# 780-00019_Rev2_Pg1.net
KiCad netlist of a schematic drawn in Altium Designer
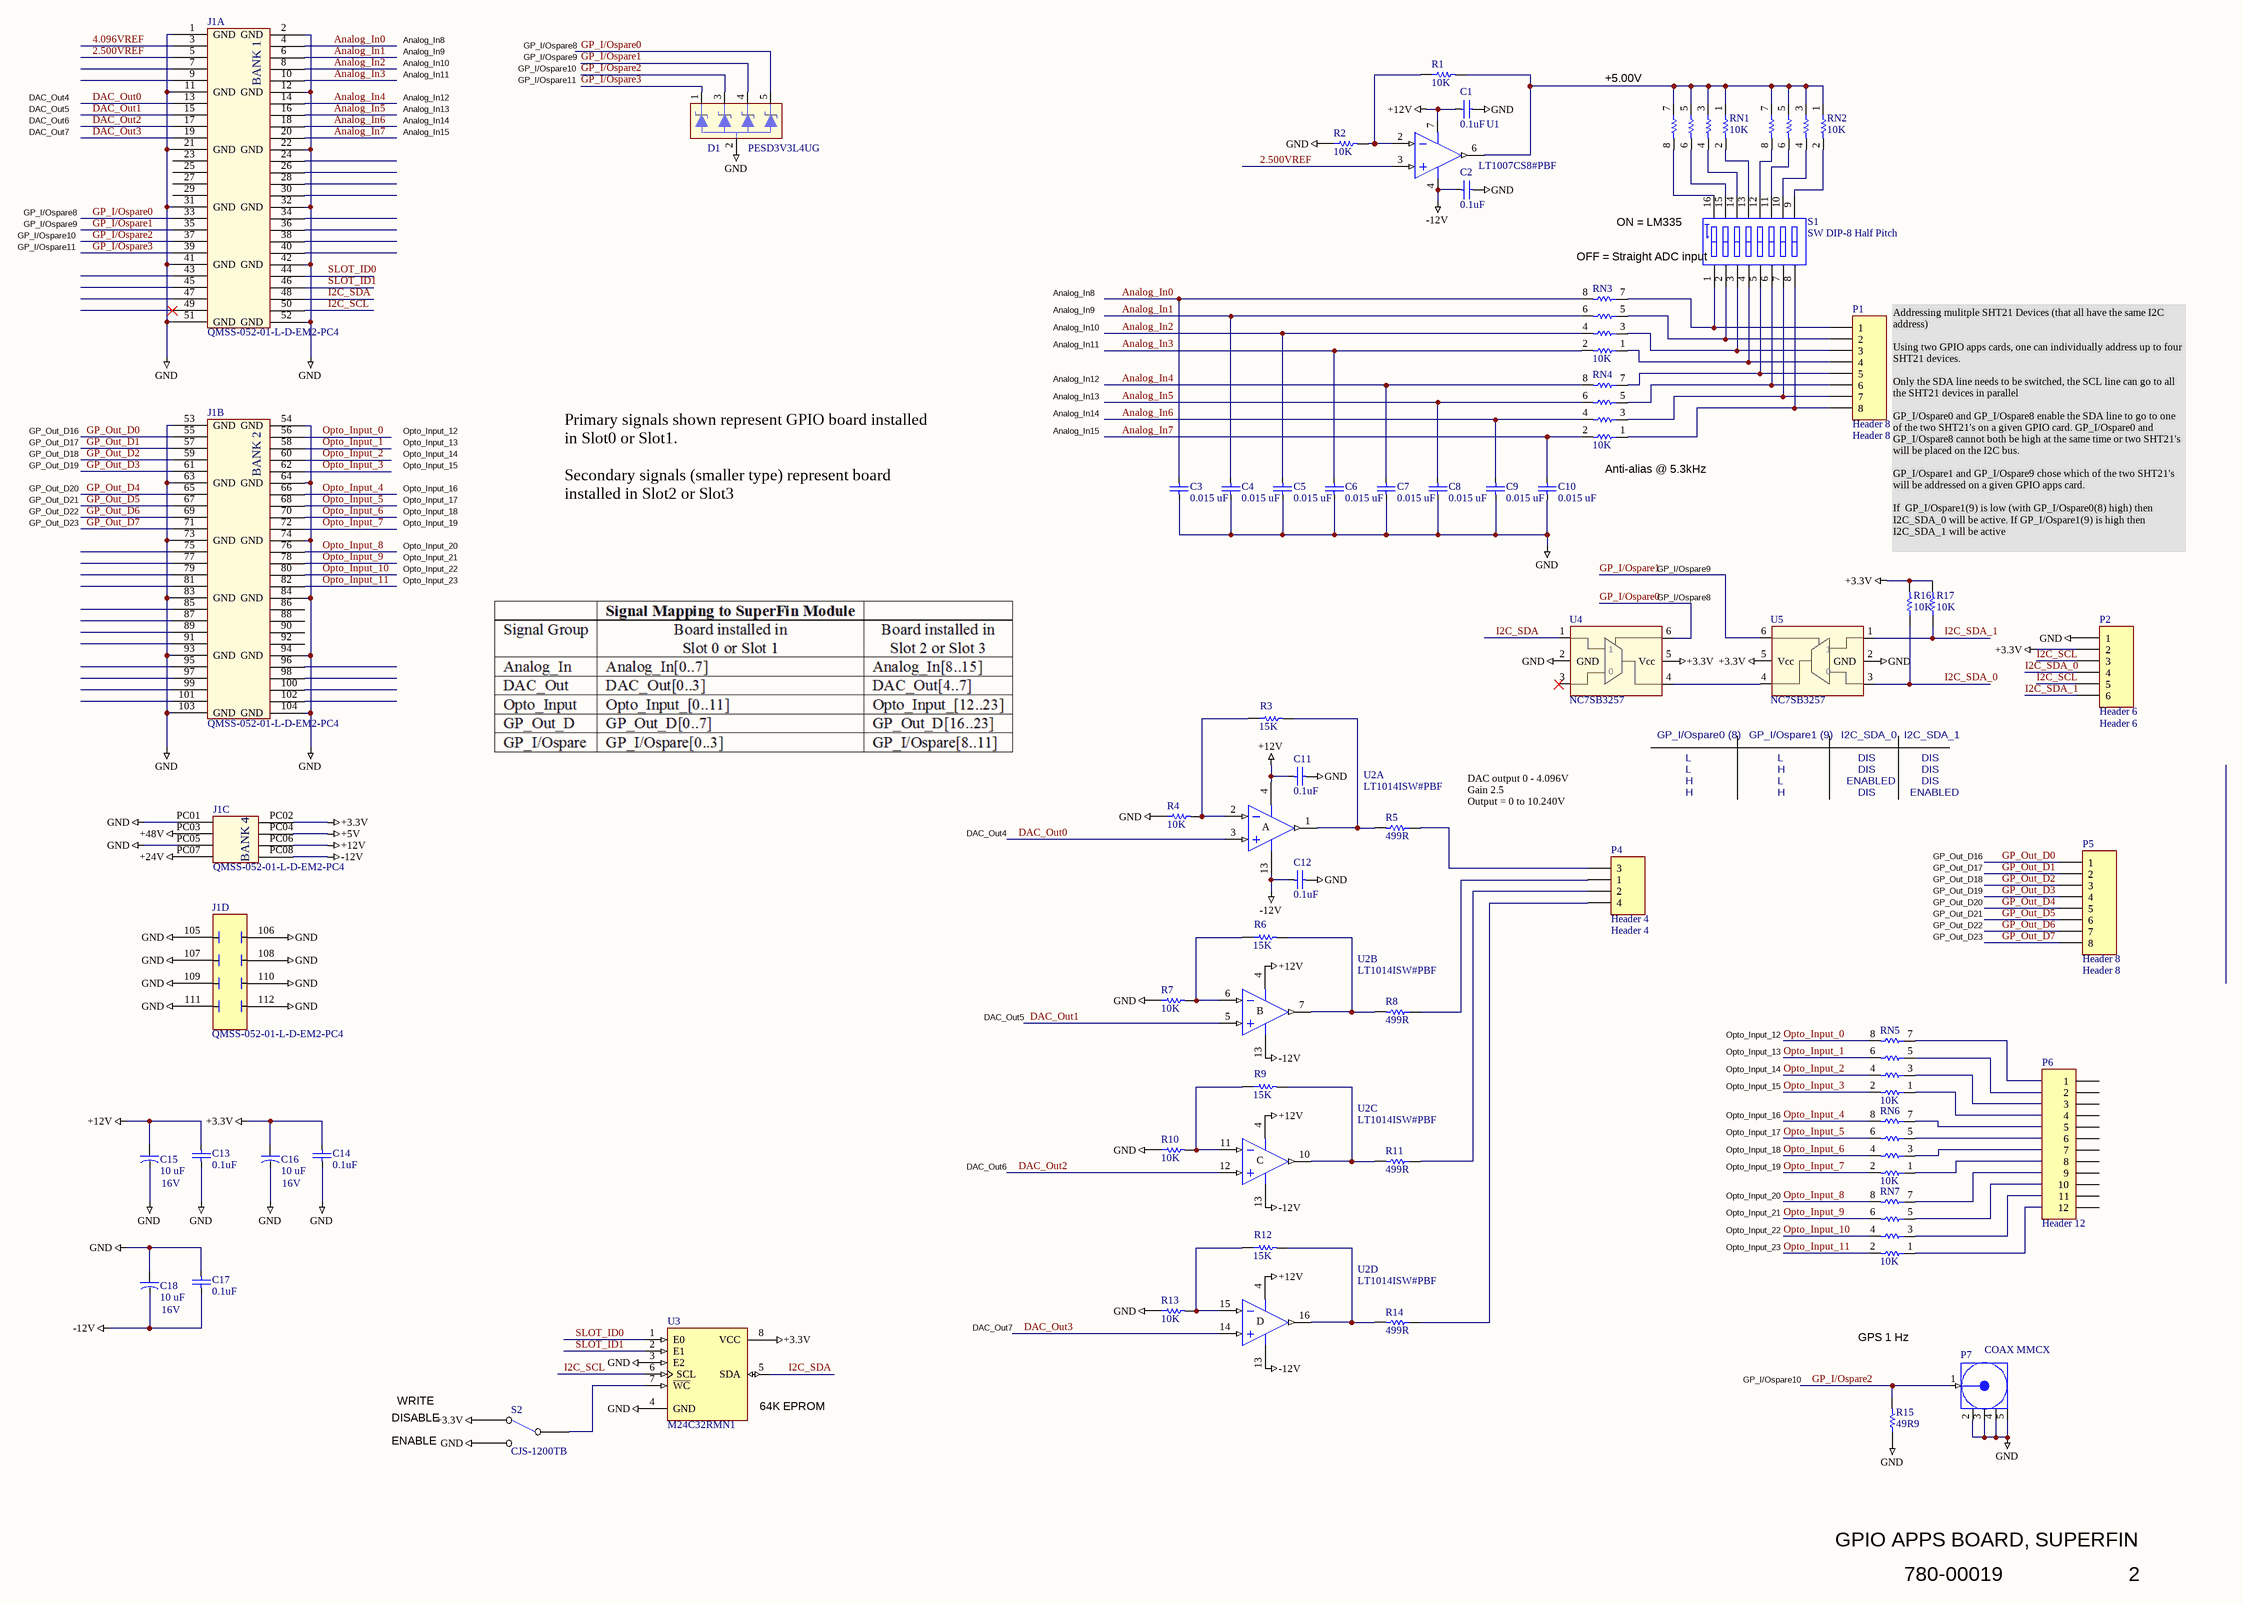
[diagram p0: 780-00019 Rev2 Pg1.SchDoc]

(export (version "E")
  (design (tool "Eeschema 10.0.6"))
  (components
    (comp (ref "C1")
      (value "0.1uF")
      (footprint "SMD_0805")
      (description "Capacitor")
      (fields (field (name "Comment") "Cap SMD"))
      (libsource (lib "Richs Schematic Components") (part "Cap SMD"))
    )
    (comp (ref "C2")
      (value "0.1uF")
      (footprint "SMD_0805")
      (description "Capacitor")
      (fields (field (name "Comment") "Cap SMD"))
      (libsource (lib "Richs Schematic Components") (part "Cap SMD"))
    )
    (comp (ref "C3")
      (value "0.015 uF")
      (footprint "SMD_0805")
      (description "Capacitor NP0")
      (fields (field (name "MANUFACTURER") "Murata") (field (name "Comment") "Cap SMD"))
      (libsource (lib "Richs Schematic Components") (part "Cap SMD"))
    )
    (comp (ref "C4")
      (value "0.015 uF")
      (footprint "SMD_0805")
      (description "Capacitor NP0")
      (fields (field (name "MANUFACTURER") "Murata") (field (name "Comment") "Cap SMD"))
      (libsource (lib "Richs Schematic Components") (part "Cap SMD"))
    )
    (comp (ref "C5")
      (value "0.015 uF")
      (footprint "SMD_0805")
      (description "Capacitor NP0")
      (fields (field (name "MANUFACTURER") "Murata") (field (name "Comment") "Cap SMD"))
      (libsource (lib "Richs Schematic Components") (part "Cap SMD"))
    )
    (comp (ref "C6")
      (value "0.015 uF")
      (footprint "SMD_0805")
      (description "Capacitor NP0")
      (fields (field (name "MANUFACTURER") "Murata") (field (name "Comment") "Cap SMD"))
      (libsource (lib "Richs Schematic Components") (part "Cap SMD"))
    )
    (comp (ref "C7")
      (value "0.015 uF")
      (footprint "SMD_0805")
      (description "Capacitor NP0")
      (fields (field (name "MANUFACTURER") "Murata") (field (name "Comment") "Cap SMD"))
      (libsource (lib "Richs Schematic Components") (part "Cap SMD"))
    )
    (comp (ref "C8")
      (value "0.015 uF")
      (footprint "SMD_0805")
      (description "Capacitor NP0")
      (fields (field (name "MANUFACTURER") "Murata") (field (name "Comment") "Cap SMD"))
      (libsource (lib "Richs Schematic Components") (part "Cap SMD"))
    )
    (comp (ref "C9")
      (value "0.015 uF")
      (footprint "SMD_0805")
      (description "Capacitor NP0")
      (fields (field (name "MANUFACTURER") "Murata") (field (name "Comment") "Cap SMD"))
      (libsource (lib "Richs Schematic Components") (part "Cap SMD"))
    )
    (comp (ref "C10")
      (value "0.015 uF")
      (footprint "SMD_0805")
      (description "Capacitor NP0")
      (fields (field (name "MANUFACTURER") "Murata") (field (name "Comment") "Cap SMD"))
      (libsource (lib "Richs Schematic Components") (part "Cap SMD"))
    )
    (comp (ref "C11")
      (value "0.1uF")
      (footprint "SMD_0805")
      (description "Capacitor")
      (fields (field (name "Comment") "Cap SMD"))
      (libsource (lib "Richs Schematic Components") (part "Cap SMD"))
    )
    (comp (ref "C12")
      (value "0.1uF")
      (footprint "SMD_0805")
      (description "Capacitor")
      (fields (field (name "Comment") "Cap SMD"))
      (libsource (lib "Richs Schematic Components") (part "Cap SMD"))
    )
    (comp (ref "C13")
      (value "0.1uF")
      (footprint "SMD_0805")
      (description "Capacitor")
      (fields (field (name "Comment") "Cap SMD"))
      (libsource (lib "Richs Schematic Components") (part "Cap SMD"))
    )
    (comp (ref "C14")
      (value "0.1uF")
      (footprint "SMD_0805")
      (description "Capacitor")
      (fields (field (name "Comment") "Cap SMD"))
      (libsource (lib "Richs Schematic Components") (part "Cap SMD"))
    )
    (comp (ref "C15")
      (value "16V")
      (footprint "SMD_CAP_3216")
      (description "outline 3.2mm x 1.6mm")
      (fields (field (name "MANUFACTURER") "KEMET") (field (name "ALTIUM_VALUE") "10 uF"))
      (libsource (lib "Richs Schematic Components") (part "Cap Tant 16V"))
    )
    (comp (ref "C16")
      (value "16V")
      (footprint "SMD_CAP_3216")
      (description "outline 3.2mm x 1.6mm")
      (fields (field (name "MANUFACTURER") "KEMET") (field (name "ALTIUM_VALUE") "10 uF"))
      (libsource (lib "Richs Schematic Components") (part "Cap Tant 16V"))
    )
    (comp (ref "C17")
      (value "0.1uF")
      (footprint "SMD_0805")
      (description "Capacitor")
      (fields (field (name "Comment") "Cap SMD"))
      (libsource (lib "Richs Schematic Components") (part "Cap SMD"))
    )
    (comp (ref "C18")
      (value "16V")
      (footprint "SMD_CAP_3216")
      (description "outline 3.2mm x 1.6mm")
      (fields (field (name "MANUFACTURER") "KEMET") (field (name "ALTIUM_VALUE") "10 uF"))
      (libsource (lib "Richs Schematic Components") (part "Cap Tant 16V"))
    )
    (comp (ref "D1")
      (value "PESD3V3L4UG")
      (footprint "SOT-353")
      (description "Quad ESD Diode 3.3V")
      (fields (field (name "MANUFACTURER") "NXP"))
      (libsource (lib "Richs Schematic Components") (part "ESD Diode 3.3V Quad"))
    )
    (comp (ref "J1")
      (value "QMSS-052-01-L-D-EM2-PC4")
      (footprint "QMS EDGE PWR PINS - 104 pin")
      (description "SAMTEC QMSS EDGE W/PWR PINS")
      (fields (field (name "MANUFACTURER") "SAMTEC") (field (name "Comment") "QMSS-EM-PC4-104pin"))
      (libsource (lib "Richs Schematic Components") (part "QMSS-EM-PC4-104pin"))
    )
    (comp (ref "P1")
      (value "Header 8")
      (footprint "HDR1X8 for IDC")
      (description "Header, 8-Pin")
      (fields (field (name "MANUFACTURER") "tyco") (field (name "ALTIUM_VALUE") "Header 8"))
      (libsource (lib "Richs Schematic Components") (part "Header 8"))
    )
    (comp (ref "P2")
      (value "Header 6")
      (footprint "HDR1X6 for IDC")
      (description "Header, 6-Pin")
      (fields (field (name "ALTIUM_VALUE") "Header 6"))
      (libsource (lib "Richs Schematic Components") (part "Header 6"))
    )
    (comp (ref "P4")
      (value "Header 4")
      (footprint "HDR1X4 for IDC")
      (description "Header, 4-Pin")
      (fields (field (name "ALTIUM_VALUE") "Header 4"))
      (libsource (lib "Richs Schematic Components") (part "Header 4"))
    )
    (comp (ref "P5")
      (value "Header 8")
      (footprint "HDR1X8 for IDC")
      (description "Header, 8-Pin")
      (fields (field (name "MANUFACTURER") "tyco") (field (name "ALTIUM_VALUE") "Header 8"))
      (libsource (lib "Richs Schematic Components") (part "Header 8"))
    )
    (comp (ref "P6")
      (value "Header 12")
      (footprint "HDR1X12 for IDC")
      (description "Header, 12-Pin")
      (fields (field (name "MANUFACTURER") "Tyco"))
      (libsource (lib "Richs Schematic Components") (part "Header 12"))
    )
    (comp (ref "P7")
      (value "COAX MMCX")
      (footprint "Miscellaneous Connectors:MMCX2.54-V5")
      (description "RF Coaxial PCB Connector, MMCX; Thru-Hole, Vertical Mount Plug,  50 Ohm Impedance")
      (fields (field (name "MANUFACTURER") "Emerson"))
      (libsource (lib "Richs Schematic Components") (part "COAX-M"))
    )
    (comp (ref "R1")
      (value "10K")
      (footprint "SMD_0805")
      (description "Resistor 0805")
      (fields (field (name "MANUFACTURER") "Vishay/Dale") (field (name "Comment") "Res 0805"))
      (libsource (lib "Richs Schematic Components") (part "Res SMD"))
    )
    (comp (ref "R2")
      (value "10K")
      (footprint "SMD_0805")
      (description "Resistor 0805")
      (fields (field (name "MANUFACTURER") "Vishay/Dale") (field (name "Comment") "Res 0805"))
      (libsource (lib "Richs Schematic Components") (part "Res SMD"))
    )
    (comp (ref "R3")
      (value "15K")
      (footprint "SMD_0805")
      (description "Resistor 0805")
      (fields (field (name "MANUFACTURER") "Vishay/Dale") (field (name "Comment") "Res 0805"))
      (libsource (lib "Richs Schematic Components") (part "Res SMD"))
    )
    (comp (ref "R4")
      (value "10K")
      (footprint "SMD_0805")
      (description "Resistor 0805")
      (fields (field (name "MANUFACTURER") "Vishay/Dale") (field (name "Comment") "Res 0805"))
      (libsource (lib "Richs Schematic Components") (part "Res SMD"))
    )
    (comp (ref "R5")
      (value "499R")
      (footprint "SMD_0805")
      (description "Resistor 0805")
      (fields (field (name "MANUFACTURER") "Vishay/Dale") (field (name "Comment") "Res 0805"))
      (libsource (lib "Richs Schematic Components") (part "Res SMD"))
    )
    (comp (ref "R6")
      (value "15K")
      (footprint "SMD_0805")
      (description "Resistor 0805")
      (fields (field (name "MANUFACTURER") "Vishay/Dale") (field (name "Comment") "Res 0805"))
      (libsource (lib "Richs Schematic Components") (part "Res SMD"))
    )
    (comp (ref "R7")
      (value "10K")
      (footprint "SMD_0805")
      (description "Resistor 0805")
      (fields (field (name "MANUFACTURER") "Vishay/Dale") (field (name "Comment") "Res 0805"))
      (libsource (lib "Richs Schematic Components") (part "Res SMD"))
    )
    (comp (ref "R8")
      (value "499R")
      (footprint "SMD_0805")
      (description "Resistor 0805")
      (fields (field (name "MANUFACTURER") "Vishay/Dale") (field (name "Comment") "Res 0805"))
      (libsource (lib "Richs Schematic Components") (part "Res SMD"))
    )
    (comp (ref "R9")
      (value "15K")
      (footprint "SMD_0805")
      (description "Resistor 0805")
      (fields (field (name "MANUFACTURER") "Vishay/Dale") (field (name "Comment") "Res 0805"))
      (libsource (lib "Richs Schematic Components") (part "Res SMD"))
    )
    (comp (ref "R10")
      (value "10K")
      (footprint "SMD_0805")
      (description "Resistor 0805")
      (fields (field (name "MANUFACTURER") "Vishay/Dale") (field (name "Comment") "Res 0805"))
      (libsource (lib "Richs Schematic Components") (part "Res SMD"))
    )
    (comp (ref "R11")
      (value "499R")
      (footprint "SMD_0805")
      (description "Resistor 0805")
      (fields (field (name "MANUFACTURER") "Vishay/Dale") (field (name "Comment") "Res 0805"))
      (libsource (lib "Richs Schematic Components") (part "Res SMD"))
    )
    (comp (ref "R12")
      (value "15K")
      (footprint "SMD_0805")
      (description "Resistor 0805")
      (fields (field (name "MANUFACTURER") "Vishay/Dale") (field (name "Comment") "Res 0805"))
      (libsource (lib "Richs Schematic Components") (part "Res SMD"))
    )
    (comp (ref "R13")
      (value "10K")
      (footprint "SMD_0805")
      (description "Resistor 0805")
      (fields (field (name "MANUFACTURER") "Vishay/Dale") (field (name "Comment") "Res 0805"))
      (libsource (lib "Richs Schematic Components") (part "Res SMD"))
    )
    (comp (ref "R14")
      (value "499R")
      (footprint "SMD_0805")
      (description "Resistor 0805")
      (fields (field (name "MANUFACTURER") "Vishay/Dale") (field (name "Comment") "Res 0805"))
      (libsource (lib "Richs Schematic Components") (part "Res SMD"))
    )
    (comp (ref "R15")
      (value "49R9")
      (footprint "SMD_0805")
      (description "Resistor 0805")
      (fields (field (name "MANUFACTURER") "Vishay/Dale") (field (name "Comment") "Res 0805"))
      (libsource (lib "Richs Schematic Components") (part "Res SMD"))
    )
    (comp (ref "R16")
      (value "10K")
      (footprint "SMD_0805")
      (description "Resistor 0805")
      (fields (field (name "MANUFACTURER") "Vishay/Dale") (field (name "Comment") "Res 0805"))
      (libsource (lib "Richs Schematic Components") (part "Res SMD"))
    )
    (comp (ref "R17")
      (value "10K")
      (footprint "SMD_0805")
      (description "Resistor 0805")
      (fields (field (name "MANUFACTURER") "Vishay/Dale") (field (name "Comment") "Res 0805"))
      (libsource (lib "Richs Schematic Components") (part "Res SMD"))
    )
    (comp (ref "RN1")
      (value "10K")
      (footprint "RES ARRAY 0603 x 4")
      (description "Resistor Array 4 Isolated")
      (fields (field (name "MANUFACTURER") "PANASONIC - ECG") (field (name "Comment") "RES ARRAY  x4 10K"))
      (libsource (lib "Richs Schematic Components") (part "RES ARRAY  x4 10K"))
    )
    (comp (ref "RN2")
      (value "10K")
      (footprint "RES ARRAY 0603 x 4")
      (description "Resistor Array 4 Isolated")
      (fields (field (name "MANUFACTURER") "PANASONIC - ECG") (field (name "Comment") "RES ARRAY  x4 10K"))
      (libsource (lib "Richs Schematic Components") (part "RES ARRAY  x4 10K"))
    )
    (comp (ref "RN3")
      (value "10K")
      (footprint "RES ARRAY 0603 x 4")
      (description "Resistor Array 4 Isolated")
      (fields (field (name "MANUFACTURER") "PANASONIC - ECG") (field (name "Comment") "RES ARRAY  x4 10K"))
      (libsource (lib "Richs Schematic Components") (part "RES ARRAY  x4 10K"))
    )
    (comp (ref "RN4")
      (value "10K")
      (footprint "RES ARRAY 0603 x 4")
      (description "Resistor Array 4 Isolated")
      (fields (field (name "MANUFACTURER") "PANASONIC - ECG") (field (name "Comment") "RES ARRAY  x4 10K"))
      (libsource (lib "Richs Schematic Components") (part "RES ARRAY  x4 10K"))
    )
    (comp (ref "RN5")
      (value "10K")
      (footprint "RES ARRAY 0603 x 4")
      (description "Resistor Array 4 Isolated")
      (fields (field (name "MANUFACTURER") "PANASONIC - ECG") (field (name "Comment") "RES ARRAY  x4 10K"))
      (libsource (lib "Richs Schematic Components") (part "RES ARRAY  x4 10K"))
    )
    (comp (ref "RN6")
      (value "10K")
      (footprint "RES ARRAY 0603 x 4")
      (description "Resistor Array 4 Isolated")
      (fields (field (name "MANUFACTURER") "PANASONIC - ECG") (field (name "Comment") "RES ARRAY  x4 10K"))
      (libsource (lib "Richs Schematic Components") (part "RES ARRAY  x4 10K"))
    )
    (comp (ref "RN7")
      (value "10K")
      (footprint "RES ARRAY 0603 x 4")
      (description "Resistor Array 4 Isolated")
      (fields (field (name "MANUFACTURER") "PANASONIC - ECG") (field (name "Comment") "RES ARRAY  x4 10K"))
      (libsource (lib "Richs Schematic Components") (part "RES ARRAY  x4 10K"))
    )
    (comp (ref "S1")
      (value "SW DIP-8 Half Pitch")
      (footprint "SW DIP 8 pos half pitch")
      (description "DIP Switch, 8 Position, SPST")
      (fields (field (name "MANUFACTURER") "GrayHill"))
      (libsource (lib "Richs Schematic Components") (part "SW DIP-8 Half Pitch"))
    )
    (comp (ref "S2")
      (value "CJS-1200TB")
      (footprint "CAS-120B")
      (fields (field (name "MANUFACTURER") "Copal Electronics"))
      (libsource (lib "JON_1_Library") (part "SW_SPDT_DOUG"))
    )
    (comp (ref "U1")
      (value "LT1007CS8#PBF")
      (footprint "S8_M")
      (description "Low Noise BJT input opamp")
      (fields (field (name "MANUFACTURER") "Linear Tech"))
      (libsource (lib "Richs Schematic Components") (part "LT1007CS8#PBF"))
    )
    (comp (ref "U2")
      (value "LT1014ISW#PBF")
      (footprint "SW16_N")
      (description "Quad Precision Operational Amplifier")
      (fields (field (name "MANUFACTURER") "Linear Tech"))
      (libsource (lib "LT Operational Amplifier") (part "LT1014ISW#PBF"))
    )
    (comp (ref "U3")
      (value "M24C32RMN1")
      (footprint "SOP8_N")
      (description "32 Kbit Serial I²C Bus EEPROM")
      (fields (field (name "MANUFACTURER") "ST Micro"))
      (libsource (lib "ST Memory EEPROM Serial") (part "M24C32RMN1"))
    )
    (comp (ref "U4")
      (value "NC7SB3257")
      (footprint "SC70-LT6_M")
      (description "Mux/Demux Bus Switch")
      (fields (field (name "MANUFACTURER") "Fairchild"))
      (libsource (lib "") (part "MUX 2{colon}1_1"))
    )
    (comp (ref "U5")
      (value "NC7SB3257")
      (footprint "SC70-LT6_M")
      (description "Mux/Demux Bus Switch")
      (fields (field (name "MANUFACTURER") "Fairchild"))
      (libsource (lib "Richs Schematic Components") (part "MUX 2{colon}1"))
    )
  )
  (nets
    (net (code "1") (name "+3.3V") (class "Default")
      (node (ref "C14") (pin "1") (pinfunction "1_1") (pintype "passive"))
      (node (ref "C16") (pin "1") (pinfunction "1_1") (pintype "passive"))
      (node (ref "J1") (pin "PC02") (pinfunction "PC02_PC02") (pintype "passive"))
      (node (ref "P2") (pin "2") (pinfunction "2_2") (pintype "passive"))
      (node (ref "R16") (pin "2") (pinfunction "2_2") (pintype "passive"))
      (node (ref "R17") (pin "2") (pinfunction "2_2") (pintype "passive"))
      (node (ref "S2") (pin "3") (pinfunction "NC_3") (pintype "passive"))
      (node (ref "U3") (pin "8") (pinfunction "VCC_8") (pintype "power_in"))
      (node (ref "U4") (pin "5") (pinfunction "Vcc_5") (pintype "passive"))
      (node (ref "U5") (pin "5") (pinfunction "Vcc_5") (pintype "passive"))
    )
    (net (code "2") (name "+5V") (class "Default")
      (node (ref "J1") (pin "PC04") (pinfunction "PC04_PC04") (pintype "passive"))
    )
    (net (code "3") (name "+12V") (class "Default")
      (node (ref "C1") (pin "1") (pinfunction "1_1") (pintype "passive"))
      (node (ref "C11") (pin "1") (pinfunction "1_1") (pintype "passive"))
      (node (ref "C13") (pin "1") (pinfunction "1_1") (pintype "passive"))
      (node (ref "C15") (pin "1") (pinfunction "1_1") (pintype "passive"))
      (node (ref "J1") (pin "PC06") (pinfunction "PC06_PC06") (pintype "passive"))
      (node (ref "U1") (pin "7") (pinfunction "V+_7") (pintype "power_in"))
      (node (ref "U2") (pin "4") (pinfunction "V+_4") (pintype "power_in"))
    )
    (net (code "4") (name "+24V") (class "Default")
      (node (ref "J1") (pin "PC07") (pinfunction "PC07_PC07") (pintype "passive"))
    )
    (net (code "5") (name "+48V") (class "Default")
      (node (ref "J1") (pin "PC03") (pinfunction "PC03_PC03") (pintype "passive"))
    )
    (net (code "6") (name "-12V") (class "Default")
      (node (ref "C12") (pin "1") (pinfunction "1_1") (pintype "passive"))
      (node (ref "C17") (pin "2") (pinfunction "2_2") (pintype "passive"))
      (node (ref "C18") (pin "2") (pinfunction "2_2") (pintype "passive"))
      (node (ref "C2") (pin "1") (pinfunction "1_1") (pintype "passive"))
      (node (ref "J1") (pin "PC08") (pinfunction "PC08_PC08") (pintype "passive"))
      (node (ref "U1") (pin "4") (pinfunction "V-_4") (pintype "power_in"))
      (node (ref "U2") (pin "13") (pinfunction "V-_13") (pintype "power_in"))
    )
    (net (code "7") (name "/2.500VREF") (class "Default")
      (node (ref "J1") (pin "5") (pinfunction "5_5") (pintype "passive"))
      (node (ref "U1") (pin "3") (pinfunction "IN+_3") (pintype "input"))
    )
    (net (code "8") (name "/4.096VREF") (class "Default")
      (node (ref "J1") (pin "3") (pinfunction "3_3") (pintype "passive"))
    )
    (net (code "9") (name "/Analog_In0") (class "Default")
      (node (ref "C3") (pin "2") (pinfunction "2_2") (pintype "passive"))
      (node (ref "J1") (pin "4") (pinfunction "4_4") (pintype "passive"))
      (node (ref "RN3") (pin "8") (pinfunction "8_8") (pintype "passive"))
    )
    (net (code "10") (name "/Analog_In1") (class "Default")
      (node (ref "C4") (pin "2") (pinfunction "2_2") (pintype "passive"))
      (node (ref "J1") (pin "6") (pinfunction "6_6") (pintype "passive"))
      (node (ref "RN3") (pin "6") (pinfunction "6_6") (pintype "passive"))
    )
    (net (code "11") (name "/Analog_In2") (class "Default")
      (node (ref "C5") (pin "2") (pinfunction "2_2") (pintype "passive"))
      (node (ref "J1") (pin "8") (pinfunction "8_8") (pintype "passive"))
      (node (ref "RN3") (pin "4") (pinfunction "4_4") (pintype "passive"))
    )
    (net (code "12") (name "/Analog_In3") (class "Default")
      (node (ref "C6") (pin "2") (pinfunction "2_2") (pintype "passive"))
      (node (ref "J1") (pin "10") (pinfunction "10_10") (pintype "passive"))
      (node (ref "RN3") (pin "2") (pinfunction "2_2") (pintype "passive"))
    )
    (net (code "13") (name "/Analog_In4") (class "Default")
      (node (ref "C7") (pin "2") (pinfunction "2_2") (pintype "passive"))
      (node (ref "J1") (pin "14") (pinfunction "14_14") (pintype "passive"))
      (node (ref "RN4") (pin "8") (pinfunction "8_8") (pintype "passive"))
    )
    (net (code "14") (name "/Analog_In5") (class "Default")
      (node (ref "C8") (pin "2") (pinfunction "2_2") (pintype "passive"))
      (node (ref "J1") (pin "16") (pinfunction "16_16") (pintype "passive"))
      (node (ref "RN4") (pin "6") (pinfunction "6_6") (pintype "passive"))
    )
    (net (code "15") (name "/Analog_In6") (class "Default")
      (node (ref "C9") (pin "2") (pinfunction "2_2") (pintype "passive"))
      (node (ref "J1") (pin "18") (pinfunction "18_18") (pintype "passive"))
      (node (ref "RN4") (pin "4") (pinfunction "4_4") (pintype "passive"))
    )
    (net (code "16") (name "/Analog_In7") (class "Default")
      (node (ref "C10") (pin "2") (pinfunction "2_2") (pintype "passive"))
      (node (ref "J1") (pin "20") (pinfunction "20_20") (pintype "passive"))
      (node (ref "RN4") (pin "2") (pinfunction "2_2") (pintype "passive"))
    )
    (net (code "17") (name "/DAC_Out0") (class "Default")
      (node (ref "J1") (pin "13") (pinfunction "13_13") (pintype "passive"))
      (node (ref "U2") (pin "3") (pinfunction "IN+_3") (pintype "input"))
    )
    (net (code "18") (name "/DAC_Out1") (class "Default")
      (node (ref "J1") (pin "15") (pinfunction "15_15") (pintype "passive"))
      (node (ref "U2") (pin "5") (pinfunction "IN+_5") (pintype "input"))
    )
    (net (code "19") (name "/DAC_Out2") (class "Default")
      (node (ref "J1") (pin "17") (pinfunction "17_17") (pintype "passive"))
      (node (ref "U2") (pin "12") (pinfunction "IN+_12") (pintype "input"))
    )
    (net (code "20") (name "/DAC_Out3") (class "Default")
      (node (ref "J1") (pin "19") (pinfunction "19_19") (pintype "passive"))
      (node (ref "U2") (pin "14") (pinfunction "IN+_14") (pintype "input"))
    )
    (net (code "21") (name "/GP_I{slash}Ospare0") (class "Default")
      (node (ref "D1") (pin "5") (pintype "passive"))
      (node (ref "J1") (pin "33") (pinfunction "33_33") (pintype "passive"))
      (node (ref "U4") (pin "6") (pinfunction "S_6") (pintype "passive"))
    )
    (net (code "22") (name "/GP_I{slash}Ospare1") (class "Default")
      (node (ref "D1") (pin "4") (pintype "passive"))
      (node (ref "J1") (pin "35") (pinfunction "35_35") (pintype "passive"))
      (node (ref "U5") (pin "6") (pinfunction "S_6") (pintype "passive"))
    )
    (net (code "23") (name "/GP_I{slash}Ospare2") (class "Default")
      (node (ref "D1") (pin "3") (pintype "passive"))
      (node (ref "J1") (pin "37") (pinfunction "37_37") (pintype "passive"))
      (node (ref "P7") (pin "1") (pinfunction "Signal_1") (pintype "input"))
      (node (ref "R15") (pin "2") (pinfunction "2_2") (pintype "passive"))
    )
    (net (code "24") (name "/GP_I{slash}Ospare3") (class "Default")
      (node (ref "D1") (pin "1") (pintype "passive"))
      (node (ref "J1") (pin "39") (pinfunction "39_39") (pintype "passive"))
    )
    (net (code "25") (name "/GP_Out_D0") (class "Default")
      (node (ref "J1") (pin "55") (pinfunction "55_55") (pintype "passive"))
      (node (ref "P5") (pin "1") (pinfunction "1_1") (pintype "passive"))
    )
    (net (code "26") (name "/GP_Out_D1") (class "Default")
      (node (ref "J1") (pin "57") (pinfunction "57_57") (pintype "passive"))
      (node (ref "P5") (pin "2") (pinfunction "2_2") (pintype "passive"))
    )
    (net (code "27") (name "/GP_Out_D2") (class "Default")
      (node (ref "J1") (pin "59") (pinfunction "59_59") (pintype "passive"))
      (node (ref "P5") (pin "3") (pinfunction "3_3") (pintype "passive"))
    )
    (net (code "28") (name "/GP_Out_D3") (class "Default")
      (node (ref "J1") (pin "61") (pinfunction "61_61") (pintype "passive"))
      (node (ref "P5") (pin "4") (pinfunction "4_4") (pintype "passive"))
    )
    (net (code "29") (name "/GP_Out_D4") (class "Default")
      (node (ref "J1") (pin "65") (pinfunction "65_65") (pintype "passive"))
      (node (ref "P5") (pin "5") (pinfunction "5_5") (pintype "passive"))
    )
    (net (code "30") (name "/GP_Out_D5") (class "Default")
      (node (ref "J1") (pin "67") (pinfunction "67_67") (pintype "passive"))
      (node (ref "P5") (pin "6") (pinfunction "6_6") (pintype "passive"))
    )
    (net (code "31") (name "/GP_Out_D6") (class "Default")
      (node (ref "J1") (pin "69") (pinfunction "69_69") (pintype "passive"))
      (node (ref "P5") (pin "7") (pinfunction "7_7") (pintype "passive"))
    )
    (net (code "32") (name "/GP_Out_D7") (class "Default")
      (node (ref "J1") (pin "71") (pinfunction "71_71") (pintype "passive"))
      (node (ref "P5") (pin "8") (pinfunction "8_8") (pintype "passive"))
    )
    (net (code "33") (name "/I2C_SCL") (class "Default")
      (node (ref "J1") (pin "50") (pinfunction "50_50") (pintype "passive"))
      (node (ref "P2") (pin "3") (pinfunction "3_3") (pintype "passive"))
      (node (ref "P2") (pin "5") (pinfunction "5_5") (pintype "passive"))
      (node (ref "U3") (pin "6") (pinfunction "SCL_6") (pintype "input"))
    )
    (net (code "34") (name "/I2C_SDA") (class "Default")
      (node (ref "J1") (pin "48") (pinfunction "48_48") (pintype "passive"))
      (node (ref "U3") (pin "5") (pinfunction "SDA_5") (pintype "bidirectional"))
      (node (ref "U4") (pin "1") (pinfunction "B1_1") (pintype "passive"))
    )
    (net (code "35") (name "/I2C_SDA_0") (class "Default")
      (node (ref "P2") (pin "4") (pinfunction "4_4") (pintype "passive"))
      (node (ref "R16") (pin "1") (pinfunction "1_1") (pintype "passive"))
      (node (ref "U5") (pin "3") (pinfunction "B0_3") (pintype "passive"))
    )
    (net (code "36") (name "/I2C_SDA_1") (class "Default")
      (node (ref "P2") (pin "6") (pinfunction "6_6") (pintype "passive"))
      (node (ref "R17") (pin "1") (pinfunction "1_1") (pintype "passive"))
      (node (ref "U5") (pin "1") (pinfunction "B1_1") (pintype "passive"))
    )
    (net (code "37") (name "/Opto_Input_0") (class "Default")
      (node (ref "J1") (pin "56") (pinfunction "56_56") (pintype "passive"))
      (node (ref "RN5") (pin "8") (pinfunction "8_8") (pintype "passive"))
    )
    (net (code "38") (name "/Opto_Input_1") (class "Default")
      (node (ref "J1") (pin "58") (pinfunction "58_58") (pintype "passive"))
      (node (ref "RN5") (pin "6") (pinfunction "6_6") (pintype "passive"))
    )
    (net (code "39") (name "/Opto_Input_2") (class "Default")
      (node (ref "J1") (pin "60") (pinfunction "60_60") (pintype "passive"))
      (node (ref "RN5") (pin "4") (pinfunction "4_4") (pintype "passive"))
    )
    (net (code "40") (name "/Opto_Input_3") (class "Default")
      (node (ref "J1") (pin "62") (pinfunction "62_62") (pintype "passive"))
      (node (ref "RN5") (pin "2") (pinfunction "2_2") (pintype "passive"))
    )
    (net (code "41") (name "/Opto_Input_4") (class "Default")
      (node (ref "J1") (pin "66") (pinfunction "66_66") (pintype "passive"))
      (node (ref "RN6") (pin "8") (pinfunction "8_8") (pintype "passive"))
    )
    (net (code "42") (name "/Opto_Input_5") (class "Default")
      (node (ref "J1") (pin "68") (pinfunction "68_68") (pintype "passive"))
      (node (ref "RN6") (pin "6") (pinfunction "6_6") (pintype "passive"))
    )
    (net (code "43") (name "/Opto_Input_6") (class "Default")
      (node (ref "J1") (pin "70") (pinfunction "70_70") (pintype "passive"))
      (node (ref "RN6") (pin "4") (pinfunction "4_4") (pintype "passive"))
    )
    (net (code "44") (name "/Opto_Input_7") (class "Default")
      (node (ref "J1") (pin "72") (pinfunction "72_72") (pintype "passive"))
      (node (ref "RN6") (pin "2") (pinfunction "2_2") (pintype "passive"))
    )
    (net (code "45") (name "/Opto_Input_8") (class "Default")
      (node (ref "J1") (pin "76") (pinfunction "76_76") (pintype "passive"))
      (node (ref "RN7") (pin "8") (pinfunction "8_8") (pintype "passive"))
    )
    (net (code "46") (name "/Opto_Input_9") (class "Default")
      (node (ref "J1") (pin "78") (pinfunction "78_78") (pintype "passive"))
      (node (ref "RN7") (pin "6") (pinfunction "6_6") (pintype "passive"))
    )
    (net (code "47") (name "/Opto_Input_10") (class "Default")
      (node (ref "J1") (pin "80") (pinfunction "80_80") (pintype "passive"))
      (node (ref "RN7") (pin "4") (pinfunction "4_4") (pintype "passive"))
    )
    (net (code "48") (name "/Opto_Input_11") (class "Default")
      (node (ref "J1") (pin "82") (pinfunction "82_82") (pintype "passive"))
      (node (ref "RN7") (pin "2") (pinfunction "2_2") (pintype "passive"))
    )
    (net (code "49") (name "/SLOT_ID0") (class "Default")
      (node (ref "J1") (pin "44") (pinfunction "44_44") (pintype "passive"))
      (node (ref "U3") (pin "1") (pinfunction "E0_1") (pintype "input"))
    )
    (net (code "50") (name "/SLOT_ID1") (class "Default")
      (node (ref "J1") (pin "46") (pinfunction "46_46") (pintype "passive"))
      (node (ref "U3") (pin "2") (pinfunction "E1_2") (pintype "input"))
    )
    (net (code "51") (name "GND") (class "Default")
      (node (ref "C1") (pin "2") (pinfunction "2_2") (pintype "passive"))
      (node (ref "C10") (pin "1") (pinfunction "1_1") (pintype "passive"))
      (node (ref "C11") (pin "2") (pinfunction "2_2") (pintype "passive"))
      (node (ref "C12") (pin "2") (pinfunction "2_2") (pintype "passive"))
      (node (ref "C13") (pin "2") (pinfunction "2_2") (pintype "passive"))
      (node (ref "C14") (pin "2") (pinfunction "2_2") (pintype "passive"))
      (node (ref "C15") (pin "2") (pinfunction "2_2") (pintype "passive"))
      (node (ref "C16") (pin "2") (pinfunction "2_2") (pintype "passive"))
      (node (ref "C17") (pin "1") (pinfunction "1_1") (pintype "passive"))
      (node (ref "C18") (pin "1") (pinfunction "1_1") (pintype "passive"))
      (node (ref "C2") (pin "2") (pinfunction "2_2") (pintype "passive"))
      (node (ref "C3") (pin "1") (pinfunction "1_1") (pintype "passive"))
      (node (ref "C4") (pin "1") (pinfunction "1_1") (pintype "passive"))
      (node (ref "C5") (pin "1") (pinfunction "1_1") (pintype "passive"))
      (node (ref "C6") (pin "1") (pinfunction "1_1") (pintype "passive"))
      (node (ref "C7") (pin "1") (pinfunction "1_1") (pintype "passive"))
      (node (ref "C8") (pin "1") (pinfunction "1_1") (pintype "passive"))
      (node (ref "C9") (pin "1") (pinfunction "1_1") (pintype "passive"))
      (node (ref "D1") (pin "2") (pintype "passive"))
      (node (ref "J1") (pin "1") (pinfunction "GND_1") (pintype "passive"))
      (node (ref "J1") (pin "103") (pinfunction "GND_103") (pintype "passive"))
      (node (ref "J1") (pin "104") (pinfunction "GND_104") (pintype "passive"))
      (node (ref "J1") (pin "105") (pinfunction "GND_105") (pintype "passive"))
      (node (ref "J1") (pin "106") (pinfunction "GND_106") (pintype "passive"))
      (node (ref "J1") (pin "107") (pinfunction "GND_107") (pintype "passive"))
      (node (ref "J1") (pin "108") (pinfunction "GND_108") (pintype "passive"))
      (node (ref "J1") (pin "109") (pinfunction "GND_109") (pintype "passive"))
      (node (ref "J1") (pin "11") (pinfunction "GND_11") (pintype "passive"))
      (node (ref "J1") (pin "110") (pinfunction "GND_110") (pintype "passive"))
      (node (ref "J1") (pin "111") (pinfunction "GND_111") (pintype "passive"))
      (node (ref "J1") (pin "112") (pinfunction "GND_112") (pintype "passive"))
      (node (ref "J1") (pin "12") (pinfunction "GND_12") (pintype "passive"))
      (node (ref "J1") (pin "2") (pinfunction "GND_2") (pintype "passive"))
      (node (ref "J1") (pin "21") (pinfunction "GND_21") (pintype "passive"))
      (node (ref "J1") (pin "22") (pinfunction "GND_22") (pintype "passive"))
      (node (ref "J1") (pin "31") (pinfunction "GND_31") (pintype "passive"))
      (node (ref "J1") (pin "32") (pinfunction "GND_32") (pintype "passive"))
      (node (ref "J1") (pin "41") (pinfunction "GND_41") (pintype "passive"))
      (node (ref "J1") (pin "42") (pinfunction "GND_42") (pintype "passive"))
      (node (ref "J1") (pin "51") (pinfunction "GND_51") (pintype "passive"))
      (node (ref "J1") (pin "52") (pinfunction "GND_52") (pintype "passive"))
      (node (ref "J1") (pin "53") (pinfunction "GND_53") (pintype "passive"))
      (node (ref "J1") (pin "54") (pinfunction "GND_54") (pintype "passive"))
      (node (ref "J1") (pin "63") (pinfunction "GND_63") (pintype "passive"))
      (node (ref "J1") (pin "64") (pinfunction "GND_64") (pintype "passive"))
      (node (ref "J1") (pin "73") (pinfunction "GND_73") (pintype "passive"))
      (node (ref "J1") (pin "74") (pinfunction "GND_74") (pintype "passive"))
      (node (ref "J1") (pin "83") (pinfunction "GND_83") (pintype "passive"))
      (node (ref "J1") (pin "84") (pinfunction "GND_84") (pintype "passive"))
      (node (ref "J1") (pin "93") (pinfunction "GND_93") (pintype "passive"))
      (node (ref "J1") (pin "94") (pinfunction "GND_94") (pintype "passive"))
      (node (ref "J1") (pin "PC01") (pinfunction "PC01_PC01") (pintype "passive"))
      (node (ref "J1") (pin "PC05") (pinfunction "PC05_PC05") (pintype "passive"))
      (node (ref "P2") (pin "1") (pinfunction "1_1") (pintype "passive"))
      (node (ref "P7") (pin "2") (pinfunction "GND_2") (pintype "power_in"))
      (node (ref "P7") (pin "3") (pinfunction "GND_3") (pintype "power_in"))
      (node (ref "P7") (pin "4") (pinfunction "GND_4") (pintype "power_in"))
      (node (ref "P7") (pin "5") (pinfunction "GND_5") (pintype "power_in"))
      (node (ref "R10") (pin "1") (pinfunction "1_1") (pintype "passive"))
      (node (ref "R13") (pin "1") (pinfunction "1_1") (pintype "passive"))
      (node (ref "R15") (pin "1") (pinfunction "1_1") (pintype "passive"))
      (node (ref "R2") (pin "1") (pinfunction "1_1") (pintype "passive"))
      (node (ref "R4") (pin "1") (pinfunction "1_1") (pintype "passive"))
      (node (ref "R7") (pin "1") (pinfunction "1_1") (pintype "passive"))
      (node (ref "S2") (pin "1") (pinfunction "NO_1") (pintype "passive"))
      (node (ref "U3") (pin "3") (pinfunction "E2_3") (pintype "input"))
      (node (ref "U3") (pin "4") (pinfunction "GND_4") (pintype "power_in"))
      (node (ref "U4") (pin "2") (pinfunction "GND_2") (pintype "passive"))
      (node (ref "U5") (pin "2") (pinfunction "GND_2") (pintype "passive"))
    )
    (net (code "52") (name "Net-(P4-Pad1)") (class "Default")
      (node (ref "P4") (pin "1") (pinfunction "1_1") (pintype "passive"))
      (node (ref "R8") (pin "1") (pinfunction "1_1") (pintype "passive"))
    )
    (net (code "53") (name "Net-(P4-Pad2)") (class "Default")
      (node (ref "P4") (pin "2") (pinfunction "2_2") (pintype "passive"))
      (node (ref "R11") (pin "1") (pinfunction "1_1") (pintype "passive"))
    )
    (net (code "54") (name "Net-(P4-Pad3)") (class "Default")
      (node (ref "P4") (pin "3") (pinfunction "3_3") (pintype "passive"))
      (node (ref "R5") (pin "1") (pinfunction "1_1") (pintype "passive"))
    )
    (net (code "55") (name "Net-(P4-Pad4)") (class "Default")
      (node (ref "P4") (pin "4") (pinfunction "4_4") (pintype "passive"))
      (node (ref "R14") (pin "1") (pinfunction "1_1") (pintype "passive"))
    )
    (net (code "56") (name "Net-(S1-A1)") (class "Default")
      (node (ref "P1") (pin "1") (pinfunction "1_1") (pintype "passive"))
      (node (ref "RN3") (pin "7") (pinfunction "1_7") (pintype "passive"))
      (node (ref "S1") (pin "1") (pinfunction "A1_1") (pintype "passive"))
    )
    (net (code "57") (name "Net-(S1-A2)") (class "Default")
      (node (ref "P1") (pin "2") (pinfunction "2_2") (pintype "passive"))
      (node (ref "RN3") (pin "5") (pinfunction "5_5") (pintype "passive"))
      (node (ref "S1") (pin "2") (pinfunction "A2_2") (pintype "passive"))
    )
    (net (code "58") (name "Net-(S1-A3)") (class "Default")
      (node (ref "P1") (pin "3") (pinfunction "3_3") (pintype "passive"))
      (node (ref "RN3") (pin "3") (pinfunction "3_3") (pintype "passive"))
      (node (ref "S1") (pin "3") (pinfunction "A3_3") (pintype "passive"))
    )
    (net (code "59") (name "Net-(S1-A4)") (class "Default")
      (node (ref "P1") (pin "4") (pinfunction "4_4") (pintype "passive"))
      (node (ref "RN3") (pin "1") (pinfunction "1_1") (pintype "passive"))
      (node (ref "S1") (pin "4") (pinfunction "A4_4") (pintype "passive"))
    )
    (net (code "60") (name "Net-(S1-A5)") (class "Default")
      (node (ref "P1") (pin "5") (pinfunction "5_5") (pintype "passive"))
      (node (ref "RN4") (pin "7") (pinfunction "1_7") (pintype "passive"))
      (node (ref "S1") (pin "5") (pinfunction "A5_5") (pintype "passive"))
    )
    (net (code "61") (name "Net-(S1-A6)") (class "Default")
      (node (ref "P1") (pin "6") (pinfunction "6_6") (pintype "passive"))
      (node (ref "RN4") (pin "5") (pinfunction "5_5") (pintype "passive"))
      (node (ref "S1") (pin "6") (pinfunction "A6_6") (pintype "passive"))
    )
    (net (code "62") (name "Net-(S1-A7)") (class "Default")
      (node (ref "P1") (pin "7") (pinfunction "7_7") (pintype "passive"))
      (node (ref "RN4") (pin "3") (pinfunction "3_3") (pintype "passive"))
      (node (ref "S1") (pin "7") (pinfunction "A7_7") (pintype "passive"))
    )
    (net (code "63") (name "Net-(S1-A8)") (class "Default")
      (node (ref "P1") (pin "8") (pinfunction "8_8") (pintype "passive"))
      (node (ref "RN4") (pin "1") (pinfunction "1_1") (pintype "passive"))
      (node (ref "S1") (pin "8") (pinfunction "A8_8") (pintype "passive"))
    )
    (net (code "64") (name "Net-(S1-B1)") (class "Default")
      (node (ref "RN1") (pin "8") (pinfunction "8_8") (pintype "passive"))
      (node (ref "S1") (pin "16") (pinfunction "B1_16") (pintype "passive"))
    )
    (net (code "65") (name "Net-(S1-B2)") (class "Default")
      (node (ref "RN1") (pin "6") (pinfunction "6_6") (pintype "passive"))
      (node (ref "S1") (pin "15") (pinfunction "B2_15") (pintype "passive"))
    )
    (net (code "66") (name "Net-(S1-B3)") (class "Default")
      (node (ref "RN1") (pin "4") (pinfunction "4_4") (pintype "passive"))
      (node (ref "S1") (pin "14") (pinfunction "B3_14") (pintype "passive"))
    )
    (net (code "67") (name "Net-(S1-B4)") (class "Default")
      (node (ref "RN1") (pin "2") (pinfunction "2_2") (pintype "passive"))
      (node (ref "S1") (pin "13") (pinfunction "B4_13") (pintype "passive"))
    )
    (net (code "68") (name "Net-(S1-B5)") (class "Default")
      (node (ref "RN2") (pin "8") (pinfunction "8_8") (pintype "passive"))
      (node (ref "S1") (pin "12") (pinfunction "B5_12") (pintype "passive"))
    )
    (net (code "69") (name "Net-(S1-B6)") (class "Default")
      (node (ref "RN2") (pin "6") (pinfunction "6_6") (pintype "passive"))
      (node (ref "S1") (pin "11") (pinfunction "B6_11") (pintype "passive"))
    )
    (net (code "70") (name "Net-(S1-B7)") (class "Default")
      (node (ref "RN2") (pin "4") (pinfunction "4_4") (pintype "passive"))
      (node (ref "S1") (pin "10") (pinfunction "B7_10") (pintype "passive"))
    )
    (net (code "71") (name "Net-(S1-B8)") (class "Default")
      (node (ref "RN2") (pin "2") (pinfunction "2_2") (pintype "passive"))
      (node (ref "S1") (pin "9") (pinfunction "B8_9") (pintype "passive"))
    )
    (net (code "72") (name "Net-(S2-COM)") (class "Default")
      (node (ref "S2") (pin "2") (pinfunction "COM_2") (pintype "passive"))
      (node (ref "U3") (pin "7") (pinfunction "~{WC}_7") (pintype "input"))
    )
    (net (code "73") (name "Net-(U1-IN-)") (class "Default")
      (node (ref "R1") (pin "1") (pinfunction "1_1") (pintype "passive"))
      (node (ref "R2") (pin "2") (pinfunction "2_2") (pintype "passive"))
      (node (ref "U1") (pin "2") (pinfunction "IN-_2") (pintype "input"))
    )
    (net (code "74") (name "Net-(U1-OUT)") (class "Default")
      (node (ref "R1") (pin "2") (pinfunction "2_2") (pintype "passive"))
      (node (ref "RN1") (pin "1") (pinfunction "1_1") (pintype "passive"))
      (node (ref "RN1") (pin "3") (pinfunction "3_3") (pintype "passive"))
      (node (ref "RN1") (pin "5") (pinfunction "5_5") (pintype "passive"))
      (node (ref "RN1") (pin "7") (pinfunction "1_7") (pintype "passive"))
      (node (ref "RN2") (pin "1") (pinfunction "1_1") (pintype "passive"))
      (node (ref "RN2") (pin "3") (pinfunction "3_3") (pintype "passive"))
      (node (ref "RN2") (pin "5") (pinfunction "5_5") (pintype "passive"))
      (node (ref "RN2") (pin "7") (pinfunction "1_7") (pintype "passive"))
      (node (ref "U1") (pin "6") (pinfunction "OUT_6") (pintype "output"))
    )
    (net (code "75") (name "Net-(U2A-IN-)") (class "Default")
      (node (ref "R3") (pin "1") (pinfunction "1_1") (pintype "passive"))
      (node (ref "R4") (pin "2") (pinfunction "2_2") (pintype "passive"))
      (node (ref "U2") (pin "2") (pinfunction "IN-_2") (pintype "input"))
    )
    (net (code "76") (name "Net-(U2A-OUT)") (class "Default")
      (node (ref "R3") (pin "2") (pinfunction "2_2") (pintype "passive"))
      (node (ref "R5") (pin "2") (pinfunction "2_2") (pintype "passive"))
      (node (ref "U2") (pin "1") (pinfunction "OUT_1") (pintype "output"))
    )
    (net (code "77") (name "Net-(U2B-IN-)") (class "Default")
      (node (ref "R6") (pin "1") (pinfunction "1_1") (pintype "passive"))
      (node (ref "R7") (pin "2") (pinfunction "2_2") (pintype "passive"))
      (node (ref "U2") (pin "6") (pinfunction "IN-_6") (pintype "input"))
    )
    (net (code "78") (name "Net-(U2B-OUT)") (class "Default")
      (node (ref "R6") (pin "2") (pinfunction "2_2") (pintype "passive"))
      (node (ref "R8") (pin "2") (pinfunction "2_2") (pintype "passive"))
      (node (ref "U2") (pin "7") (pinfunction "OUT_7") (pintype "output"))
    )
    (net (code "79") (name "Net-(U2C-IN-)") (class "Default")
      (node (ref "R10") (pin "2") (pinfunction "2_2") (pintype "passive"))
      (node (ref "R9") (pin "1") (pinfunction "1_1") (pintype "passive"))
      (node (ref "U2") (pin "11") (pinfunction "IN-_11") (pintype "input"))
    )
    (net (code "80") (name "Net-(U2C-OUT)") (class "Default")
      (node (ref "R11") (pin "2") (pinfunction "2_2") (pintype "passive"))
      (node (ref "R9") (pin "2") (pinfunction "2_2") (pintype "passive"))
      (node (ref "U2") (pin "10") (pinfunction "OUT_10") (pintype "output"))
    )
    (net (code "81") (name "Net-(U2D-IN-)") (class "Default")
      (node (ref "R12") (pin "1") (pinfunction "1_1") (pintype "passive"))
      (node (ref "R13") (pin "2") (pinfunction "2_2") (pintype "passive"))
      (node (ref "U2") (pin "15") (pinfunction "IN-_15") (pintype "input"))
    )
    (net (code "82") (name "Net-(U2D-OUT)") (class "Default")
      (node (ref "R12") (pin "2") (pinfunction "2_2") (pintype "passive"))
      (node (ref "R14") (pin "2") (pinfunction "2_2") (pintype "passive"))
      (node (ref "U2") (pin "16") (pinfunction "OUT_16") (pintype "output"))
    )
    (net (code "83") (name "Net-(U4-A)") (class "Default")
      (node (ref "U4") (pin "4") (pinfunction "A_4") (pintype "passive"))
      (node (ref "U5") (pin "4") (pinfunction "A_4") (pintype "passive"))
    )
    (net (code "84") (name "unconnected-(J1-Pad7)") (class "Default")
      (node (ref "J1") (pin "7") (pinfunction "7_7") (pintype "passive"))
    )
    (net (code "85") (name "unconnected-(J1-Pad9)") (class "Default")
      (node (ref "J1") (pin "9") (pinfunction "9_9") (pintype "passive"))
    )
    (net (code "86") (name "unconnected-(J1-Pad23)") (class "Default")
      (node (ref "J1") (pin "23") (pinfunction "23_23") (pintype "passive"))
    )
    (net (code "87") (name "unconnected-(J1-Pad24)") (class "Default")
      (node (ref "J1") (pin "24") (pinfunction "24_24") (pintype "passive"))
    )
    (net (code "88") (name "unconnected-(J1-Pad25)") (class "Default")
      (node (ref "J1") (pin "25") (pinfunction "25_25") (pintype "passive"))
    )
    (net (code "89") (name "unconnected-(J1-Pad26)") (class "Default")
      (node (ref "J1") (pin "26") (pinfunction "26_26") (pintype "passive"))
    )
    (net (code "90") (name "unconnected-(J1-Pad27)") (class "Default")
      (node (ref "J1") (pin "27") (pinfunction "27_27") (pintype "passive"))
    )
    (net (code "91") (name "unconnected-(J1-Pad28)") (class "Default")
      (node (ref "J1") (pin "28") (pinfunction "28_28") (pintype "passive"))
    )
    (net (code "92") (name "unconnected-(J1-Pad29)") (class "Default")
      (node (ref "J1") (pin "29") (pinfunction "29_29") (pintype "passive"))
    )
    (net (code "93") (name "unconnected-(J1-Pad30)") (class "Default")
      (node (ref "J1") (pin "30") (pinfunction "30_30") (pintype "passive"))
    )
    (net (code "94") (name "unconnected-(J1-Pad34)") (class "Default")
      (node (ref "J1") (pin "34") (pinfunction "34_34") (pintype "passive"))
    )
    (net (code "95") (name "unconnected-(J1-Pad36)") (class "Default")
      (node (ref "J1") (pin "36") (pinfunction "36_36") (pintype "passive"))
    )
    (net (code "96") (name "unconnected-(J1-Pad38)") (class "Default")
      (node (ref "J1") (pin "38") (pinfunction "38_38") (pintype "passive"))
    )
    (net (code "97") (name "unconnected-(J1-Pad40)") (class "Default")
      (node (ref "J1") (pin "40") (pinfunction "40_40") (pintype "passive"))
    )
    (net (code "98") (name "unconnected-(J1-Pad43)") (class "Default")
      (node (ref "J1") (pin "43") (pinfunction "43_43") (pintype "passive"))
    )
    (net (code "99") (name "unconnected-(J1-Pad45)") (class "Default")
      (node (ref "J1") (pin "45") (pinfunction "45_45") (pintype "passive"))
    )
    (net (code "100") (name "unconnected-(J1-Pad47)") (class "Default")
      (node (ref "J1") (pin "47") (pinfunction "47_47") (pintype "passive"))
    )
    (net (code "101") (name "unconnected-(J1-Pad49)") (class "Default")
      (node (ref "J1") (pin "49") (pinfunction "49_49") (pintype "passive+no_connect"))
    )
    (net (code "102") (name "unconnected-(J1-Pad75)") (class "Default")
      (node (ref "J1") (pin "75") (pinfunction "75_75") (pintype "passive"))
    )
    (net (code "103") (name "unconnected-(J1-Pad77)") (class "Default")
      (node (ref "J1") (pin "77") (pinfunction "77_77") (pintype "passive"))
    )
    (net (code "104") (name "unconnected-(J1-Pad79)") (class "Default")
      (node (ref "J1") (pin "79") (pinfunction "79_79") (pintype "passive"))
    )
    (net (code "105") (name "unconnected-(J1-Pad81)") (class "Default")
      (node (ref "J1") (pin "81") (pinfunction "81_81") (pintype "passive"))
    )
    (net (code "106") (name "unconnected-(J1-Pad85)") (class "Default")
      (node (ref "J1") (pin "85") (pinfunction "85_85") (pintype "passive"))
    )
    (net (code "107") (name "unconnected-(J1-Pad86)") (class "Default")
      (node (ref "J1") (pin "86") (pinfunction "86_86") (pintype "passive"))
    )
    (net (code "108") (name "unconnected-(J1-Pad87)") (class "Default")
      (node (ref "J1") (pin "87") (pinfunction "87_87") (pintype "passive"))
    )
    (net (code "109") (name "unconnected-(J1-Pad88)") (class "Default")
      (node (ref "J1") (pin "88") (pinfunction "88_88") (pintype "passive"))
    )
    (net (code "110") (name "unconnected-(J1-Pad89)") (class "Default")
      (node (ref "J1") (pin "89") (pinfunction "89_89") (pintype "passive"))
    )
    (net (code "111") (name "unconnected-(J1-Pad90)") (class "Default")
      (node (ref "J1") (pin "90") (pinfunction "90_90") (pintype "passive"))
    )
    (net (code "112") (name "unconnected-(J1-Pad91)") (class "Default")
      (node (ref "J1") (pin "91") (pinfunction "91_91") (pintype "passive"))
    )
    (net (code "113") (name "unconnected-(J1-Pad92)") (class "Default")
      (node (ref "J1") (pin "92") (pinfunction "92_92") (pintype "passive"))
    )
    (net (code "114") (name "unconnected-(J1-Pad95)") (class "Default")
      (node (ref "J1") (pin "95") (pinfunction "95_95") (pintype "passive"))
    )
    (net (code "115") (name "unconnected-(J1-Pad96)") (class "Default")
      (node (ref "J1") (pin "96") (pinfunction "96_96") (pintype "passive"))
    )
    (net (code "116") (name "unconnected-(J1-Pad97)") (class "Default")
      (node (ref "J1") (pin "97") (pinfunction "97_97") (pintype "passive"))
    )
    (net (code "117") (name "unconnected-(J1-Pad98)") (class "Default")
      (node (ref "J1") (pin "98") (pinfunction "98_98") (pintype "passive"))
    )
    (net (code "118") (name "unconnected-(J1-Pad99)") (class "Default")
      (node (ref "J1") (pin "99") (pinfunction "99_99") (pintype "passive"))
    )
    (net (code "119") (name "unconnected-(J1-Pad100)") (class "Default")
      (node (ref "J1") (pin "100") (pinfunction "100_100") (pintype "passive"))
    )
    (net (code "120") (name "unconnected-(J1-Pad101)") (class "Default")
      (node (ref "J1") (pin "101") (pinfunction "101_101") (pintype "passive"))
    )
    (net (code "121") (name "unconnected-(J1-Pad102)") (class "Default")
      (node (ref "J1") (pin "102") (pinfunction "102_102") (pintype "passive"))
    )
    (net (code "122") (name "unconnected-(P6-Pad1)") (class "Default")
      (node (ref "P6") (pin "1") (pinfunction "1_1") (pintype "passive"))
    )
    (net (code "123") (name "unconnected-(P6-Pad2)") (class "Default")
      (node (ref "P6") (pin "2") (pinfunction "2_2") (pintype "passive"))
    )
    (net (code "124") (name "unconnected-(P6-Pad3)") (class "Default")
      (node (ref "P6") (pin "3") (pinfunction "3_3") (pintype "passive"))
    )
    (net (code "125") (name "unconnected-(P6-Pad4)") (class "Default")
      (node (ref "P6") (pin "4") (pinfunction "4_4") (pintype "passive"))
    )
    (net (code "126") (name "unconnected-(P6-Pad5)") (class "Default")
      (node (ref "P6") (pin "5") (pinfunction "5_5") (pintype "passive"))
    )
    (net (code "127") (name "unconnected-(P6-Pad6)") (class "Default")
      (node (ref "P6") (pin "6") (pinfunction "6_6") (pintype "passive"))
    )
    (net (code "128") (name "unconnected-(P6-Pad7)") (class "Default")
      (node (ref "P6") (pin "7") (pinfunction "7_7") (pintype "passive"))
    )
    (net (code "129") (name "unconnected-(P6-Pad8)") (class "Default")
      (node (ref "P6") (pin "8") (pinfunction "8_8") (pintype "passive"))
    )
    (net (code "130") (name "unconnected-(P6-Pad9)") (class "Default")
      (node (ref "P6") (pin "9") (pinfunction "9_9") (pintype "passive"))
    )
    (net (code "131") (name "unconnected-(P6-Pad10)") (class "Default")
      (node (ref "P6") (pin "10") (pinfunction "10_10") (pintype "passive"))
    )
    (net (code "132") (name "unconnected-(P6-Pad11)") (class "Default")
      (node (ref "P6") (pin "11") (pinfunction "11_11") (pintype "passive"))
    )
    (net (code "133") (name "unconnected-(P6-Pad12)") (class "Default")
      (node (ref "P6") (pin "12") (pinfunction "12_12") (pintype "passive"))
    )
    (net (code "134") (name "unconnected-(RN5-1-Pad7)") (class "Default")
      (node (ref "RN5") (pin "7") (pinfunction "1_7") (pintype "passive"))
    )
    (net (code "135") (name "unconnected-(RN5-Pad1)") (class "Default")
      (node (ref "RN5") (pin "1") (pinfunction "1_1") (pintype "passive"))
    )
    (net (code "136") (name "unconnected-(RN5-Pad3)") (class "Default")
      (node (ref "RN5") (pin "3") (pinfunction "3_3") (pintype "passive"))
    )
    (net (code "137") (name "unconnected-(RN5-Pad5)") (class "Default")
      (node (ref "RN5") (pin "5") (pinfunction "5_5") (pintype "passive"))
    )
    (net (code "138") (name "unconnected-(RN6-1-Pad7)") (class "Default")
      (node (ref "RN6") (pin "7") (pinfunction "1_7") (pintype "passive"))
    )
    (net (code "139") (name "unconnected-(RN6-Pad1)") (class "Default")
      (node (ref "RN6") (pin "1") (pinfunction "1_1") (pintype "passive"))
    )
    (net (code "140") (name "unconnected-(RN6-Pad3)") (class "Default")
      (node (ref "RN6") (pin "3") (pinfunction "3_3") (pintype "passive"))
    )
    (net (code "141") (name "unconnected-(RN6-Pad5)") (class "Default")
      (node (ref "RN6") (pin "5") (pinfunction "5_5") (pintype "passive"))
    )
    (net (code "142") (name "unconnected-(RN7-1-Pad7)") (class "Default")
      (node (ref "RN7") (pin "7") (pinfunction "1_7") (pintype "passive"))
    )
    (net (code "143") (name "unconnected-(RN7-Pad1)") (class "Default")
      (node (ref "RN7") (pin "1") (pinfunction "1_1") (pintype "passive"))
    )
    (net (code "144") (name "unconnected-(RN7-Pad3)") (class "Default")
      (node (ref "RN7") (pin "3") (pinfunction "3_3") (pintype "passive"))
    )
    (net (code "145") (name "unconnected-(RN7-Pad5)") (class "Default")
      (node (ref "RN7") (pin "5") (pinfunction "5_5") (pintype "passive"))
    )
    (net (code "146") (name "unconnected-(U1-NC-Pad5)") (class "Default")
      (node (ref "U1") (pin "5") (pinfunction "NC_5") (pintype "passive"))
    )
    (net (code "147") (name "unconnected-(U1-VOSTRIM-Pad1)") (class "Default")
      (node (ref "U1") (pin "1") (pinfunction "VOSTRIM_1") (pintype "passive"))
    )
    (net (code "148") (name "unconnected-(U1-VOSTRIM-Pad8)") (class "Default")
      (node (ref "U1") (pin "8") (pinfunction "VOSTRIM_8") (pintype "passive"))
    )
    (net (code "149") (name "unconnected-(U4-B0-Pad3)") (class "Default")
      (node (ref "U4") (pin "3") (pinfunction "B0_3") (pintype "passive+no_connect"))
    )
  )
)
